# Parallel_PCU_Test.net
KiCad netlist of a schematic drawn in Altium Designer
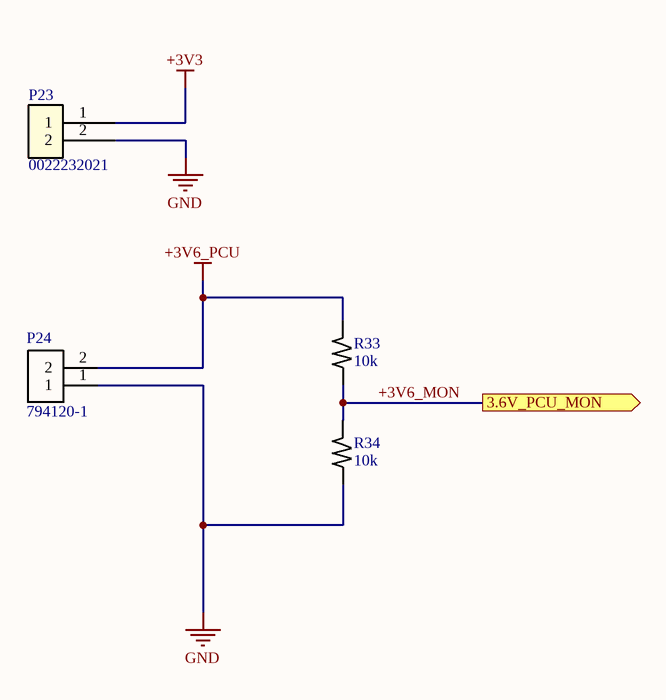
[diagram p0: Parallel PCU Test.SchDoc]

(export (version "E")
  (design (tool "Eeschema 10.0.6"))
  (components
    (comp (ref "P23")
      (value "0022232021")
      (footprint "Signal2")
      (description "SignalConnector, 2 leads")
      (fields (field (name "MF") "Molex"))
      (libsource (lib "Connectors") (part "Signal2"))
    )
    (comp (ref "P24")
      (value "794120-1")
      (footprint "POWER2-5.08 right angle")
      (fields (field (name "MP") "TE Connectivity"))
      (libsource (lib "Connectors") (part "Power2"))
    )
    (comp (ref "R33")
      (value "10k")
      (footprint "R0603")
      (description "RES 10kΩ ±1% 100mW 0603")
      (fields (field (name "MF") "FOJAN") (field (name "MP") "FRC0603F1002TS"))
      (libsource (lib "Components") (part "Res"))
    )
    (comp (ref "R34")
      (value "10k")
      (footprint "R0603")
      (description "RES 10kΩ ±1% 100mW 0603")
      (fields (field (name "MF") "FOJAN") (field (name "MP") "FRC0603F1002TS"))
      (libsource (lib "Components") (part "Res"))
    )
  )
  (nets
    (net (code "1") (name "+3V3") (class "Default")
      (node (ref "P23") (pin "1") (pinfunction "1_1") (pintype "passive"))
    )
    (net (code "2") (name "+3V6_PCU") (class "Default")
      (node (ref "P24") (pin "2") (pinfunction "2_2") (pintype "passive"))
      (node (ref "R33") (pin "2") (pinfunction "2_2") (pintype "passive"))
    )
    (net (code "3") (name "/+3V6_MON") (class "Default")
      (node (ref "R33") (pin "1") (pinfunction "1_1") (pintype "passive"))
      (node (ref "R34") (pin "2") (pinfunction "2_2") (pintype "passive"))
    )
    (net (code "4") (name "GND") (class "Default")
      (node (ref "P23") (pin "2") (pinfunction "2_2") (pintype "passive"))
      (node (ref "P24") (pin "1") (pinfunction "1_1") (pintype "passive"))
      (node (ref "R34") (pin "1") (pinfunction "1_1") (pintype "passive"))
    )
  )
)
